# psu.net
KiCad netlist of a schematic drawn in Altium Designer
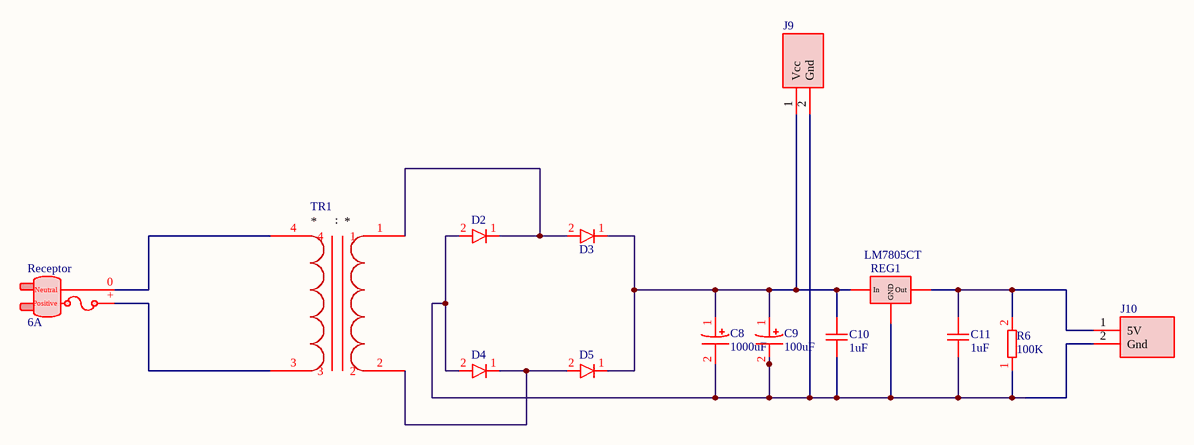
[diagram p0: psu.SchDoc]

(export (version "E")
  (design (tool "Eeschema 10.0.6"))
  (components
    (comp (ref "C8")
      (value "1000uF")
      (footprint "CAP_RAD_10x20mm_ELC")
      (description "Electrolothic radial mount Capacitor Polarised")
      (fields
        (field (name "MANUFACTURER_PART_NUMBER") "860020475018")
        (field (name "MOUSER PART NUMBER") "710-860020475018")
      )
      (libsource (lib "SolderIron") (part "D_Capacitor_Rad_ELC"))
    )
    (comp (ref "C9")
      (value "100uF")
      (footprint "CAP_RAD_ELC_5x11mm")
      (description "Electrolothic radial mount Capacitor Polarised")
      (fields
        (field (name "MANUFACTURER_PART_NUMBER") "860020475018")
        (field (name "MOUSER PART NUMBER") "710-860020475018")
      )
      (libsource (lib "SolderIron") (part "D_Capacitor_Rad_ELC"))
    )
    (comp (ref "C10")
      (value "1uF")
      (footprint "CAP_RAD_MLCC")
      (libsource (lib "SolderIron") (part "D_Capacitor_RAD_MLCC"))
    )
    (comp (ref "C11")
      (value "1uF")
      (footprint "CAP_RAD_MLCC")
      (libsource (lib "SolderIron") (part "D_Capacitor_RAD_MLCC"))
    )
    (comp (ref "D2")
      (value "D_Diode_SMC4")
      (footprint "DIO_S8KS-E3/I_MED")
      (description "General purpose SMC-4 diode")
      (fields
        (field (name "MANUFACTURER_PART_NUMBER") "S8KS-E3/I")
        (field (name "MOUSER PART NUMBER") "78-S8KS-E3/I")
      )
      (libsource (lib "SolderIron") (part "D_Diode_SMC4"))
    )
    (comp (ref "D3")
      (value "D_Diode_SMC4")
      (footprint "DIO_S8KS-E3/I_MED")
      (description "General purpose SMC-4 diode")
      (fields
        (field (name "MANUFACTURER_PART_NUMBER") "S8KS-E3/I")
        (field (name "MOUSER PART NUMBER") "78-S8KS-E3/I")
      )
      (libsource (lib "SolderIron") (part "D_Diode_SMC4"))
    )
    (comp (ref "D4")
      (value "D_Diode_SMC4")
      (footprint "DIO_S8KS-E3/I_MED")
      (description "General purpose SMC-4 diode")
      (fields
        (field (name "MANUFACTURER_PART_NUMBER") "S8KS-E3/I")
        (field (name "MOUSER PART NUMBER") "78-S8KS-E3/I")
      )
      (libsource (lib "SolderIron") (part "D_Diode_SMC4"))
    )
    (comp (ref "D5")
      (value "D_Diode_SMC4")
      (footprint "DIO_S8KS-E3/I_MED")
      (description "General purpose SMC-4 diode")
      (fields
        (field (name "MANUFACTURER_PART_NUMBER") "S8KS-E3/I")
        (field (name "MOUSER PART NUMBER") "78-S8KS-E3/I")
      )
      (libsource (lib "SolderIron") (part "D_Diode_SMC4"))
    )
    (comp (ref "J9")
      (value "CON_F1x2Pin")
      (footprint "CON_F1x2Pin")
      (description "Connector")
      (fields (field (name "MANUFACTURER_PART_NUMBER") "SMC-1-02-1-GT"))
      (libsource (lib "SolderIron") (part "CON_F1x2Pin"))
    )
    (comp (ref "J10")
      (value "CON_F1x2Pin")
      (footprint "CON_F1x2Pin")
      (description "Connector")
      (fields (field (name "MANUFACTURER_PART_NUMBER") "SMC-1-02-1-GT"))
      (libsource (lib "") (part "CON_F1x2Pin_1"))
    )
    (comp (ref "R6")
      (value "100K")
      (footprint "RES_0805US_MED")
      (description "SMD 0603 Thick Film 4.7kΩ 5.00% 0.1W")
      (fields (field (name "TOLERANCE") "5%"))
      (libsource (lib "SolderIron") (part "D_Resistor_TF0805"))
    )
    (comp (ref "Receptor") (value "6A") (libsource (lib "SolderIron") (part "INLET_ACPower")))
    (comp (ref "REG1")
      (value "LM7805CT")
      (footprint "IC_5V_REGULATOR")
      (description "Non adjustable SC voltage reg 3pin")
      (libsource (lib "SolderIron") (part "IC_Regulator"))
    )
    (comp (ref "TR1") (value "TRANS_NoTap") (libsource (lib "SolderIron") (part "TRANS_NoTap")))
  )
  (nets
    (net (code "1") (name "Net-(C8-+)") (class "Default")
      (node (ref "C10") (pin "2") (pinfunction "2_2") (pintype "passive"))
      (node (ref "C8") (pin "1") (pinfunction "+_1") (pintype "power_in"))
      (node (ref "C9") (pin "1") (pinfunction "+_1") (pintype "power_in"))
      (node (ref "D3") (pin "1") (pinfunction "K_1") (pintype "passive"))
      (node (ref "D5") (pin "1") (pinfunction "K_1") (pintype "passive"))
      (node (ref "J9") (pin "1") (pinfunction "Vcc_1") (pintype "passive"))
      (node (ref "REG1") (pin "3") (pinfunction "In_3") (pintype "passive"))
    )
    (net (code "2") (name "Net-(C8--)") (class "Default")
      (node (ref "C10") (pin "1") (pinfunction "1_1") (pintype "passive"))
      (node (ref "C11") (pin "1") (pinfunction "1_1") (pintype "passive"))
      (node (ref "C8") (pin "2") (pinfunction "-_2") (pintype "power_in"))
      (node (ref "C9") (pin "2") (pinfunction "-_2") (pintype "power_in"))
      (node (ref "D2") (pin "2") (pinfunction "A_2") (pintype "passive"))
      (node (ref "D4") (pin "2") (pinfunction "A_2") (pintype "passive"))
      (node (ref "J10") (pin "2") (pinfunction "Gnd_2") (pintype "passive"))
      (node (ref "J9") (pin "2") (pinfunction "Gnd_2") (pintype "passive"))
      (node (ref "R6") (pin "1") (pinfunction "1_1") (pintype "passive"))
      (node (ref "REG1") (pin "2") (pinfunction "GND_2") (pintype "passive"))
    )
    (net (code "3") (name "Net-(D2-K)") (class "Default")
      (node (ref "D2") (pin "1") (pinfunction "K_1") (pintype "passive"))
      (node (ref "D3") (pin "2") (pinfunction "A_2") (pintype "passive"))
      (node (ref "TR1") (pin "1") (pinfunction "1_1") (pintype "passive"))
    )
    (net (code "4") (name "Net-(D4-K)") (class "Default")
      (node (ref "D4") (pin "1") (pinfunction "K_1") (pintype "passive"))
      (node (ref "D5") (pin "2") (pinfunction "A_2") (pintype "passive"))
      (node (ref "TR1") (pin "2") (pinfunction "2_2") (pintype "passive"))
    )
    (net (code "5") (name "Net-(J10-5V)") (class "Default")
      (node (ref "C11") (pin "2") (pinfunction "2_2") (pintype "passive"))
      (node (ref "J10") (pin "1") (pinfunction "5V_1") (pintype "passive"))
      (node (ref "R6") (pin "2") (pinfunction "2_2") (pintype "passive"))
      (node (ref "REG1") (pin "1") (pinfunction "Out_1") (pintype "passive"))
    )
    (net (code "6") (name "Net-(Receptor-Neutral)") (class "Default")
      (node (ref "Receptor") (pin "0") (pinfunction "Neutral_0") (pintype "passive"))
      (node (ref "TR1") (pin "4") (pinfunction "4_4") (pintype "passive"))
    )
    (net (code "7") (name "Net-(Receptor-Positive)") (class "Default")
      (node (ref "Receptor") (pin "+") (pinfunction "Positive_+") (pintype "passive"))
      (node (ref "TR1") (pin "3") (pinfunction "3_3") (pintype "passive"))
    )
  )
)
